# Antenna.net
KiCad netlist of a schematic drawn in Altium Designer
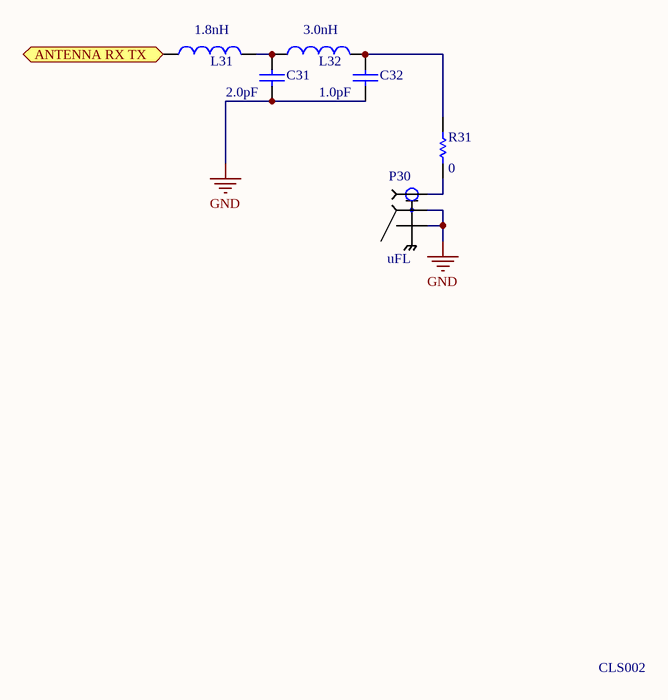
[diagram p0: Antenna.SchDoc]

(export (version "E")
  (design (tool "Eeschema 10.0.6"))
  (components
    (comp (ref "C31")
      (value "2.0pF")
      (footprint "0402_CHIP_FP")
      (fields
        (field (name "MANUFACTURER") "Murata Electronics North America")
        (field (name "MANUFACTURER PART NUMBER") "GJM1555C1H2R0WB01D")
        (field (name "VENDOR PART NUMBER") "490-11205-1-ND")
      )
      (libsource (lib "GenericSymbols") (part "Capacitor_unpolarized_0805"))
    )
    (comp (ref "C32")
      (value "1.0pF")
      (footprint "0402_CHIP_FP")
      (fields
        (field (name "MANUFACTURER") "Murata Electronics North America")
        (field (name "MANUFACTURER PART NUMBER") "GJM1555C1H1R0WB01D")
        (field (name "VENDOR PART NUMBER") "490-11193-1-ND")
      )
      (libsource (lib "GenericSymbols") (part "Capacitor_unpolarized_0805"))
    )
    (comp (ref "L31")
      (value "1.8nH")
      (footprint "0402_CHIP_FP")
      (fields
        (field (name "MANUFACTURER") "Murata Electronics North America")
        (field (name "MANUFACTURER PART NUMBER") "LQP15MN1N8B02D")
        (field (name "VENDOR PART NUMBER") "490-1127-1-ND")
      )
      (libsource (lib "GenericSymbols") (part "Inductor"))
    )
    (comp (ref "L32")
      (value "3.0nH")
      (footprint "0402_CHIP_FP")
      (fields
        (field (name "MANUFACTURER") "Murata Electronics North America")
        (field (name "MANUFACTURER PART NUMBER") "LQP15MN3N0B02D")
        (field (name "VENDOR PART NUMBER") "490-6755-1-ND")
      )
      (libsource (lib "GenericSymbols") (part "Inductor"))
    )
    (comp (ref "P30")
      (value "uFL")
      (footprint "MOLEX_1661")
      (description "uFL SMT Antenna Connector")
      (fields (field (name "MF") "Keystone Electronics") (field (name "MP") "1661"))
      (libsource (lib "1661") (part "1661"))
    )
    (comp (ref "R31")
      (value "0")
      (footprint "0805_CHIP_FP")
      (fields
        (field (name "MANUFACTURER") "Vishay Dale")
        (field (name "MANUFACTURER PART NUMBER") "CRCW08050000Z0EA")
        (field (name "VENDOR PART NUMBER") "541-0.0ACT-ND")
      )
      (libsource (lib "GenericSymbols") (part "Resistor_0805"))
    )
  )
  (nets
    (net (code "1") (name "/ANTENNA RX TX") (class "Default")
      (node (ref "L31") (pin "1") (pinfunction "1_1") (pintype "passive"))
    )
    (net (code "2") (name "GND") (class "Default")
      (node (ref "C31") (pin "1") (pinfunction "1_1") (pintype "passive"))
      (node (ref "C32") (pin "1") (pinfunction "1_1") (pintype "passive"))
      (node (ref "P30") (pin "2") (pinfunction "GND_2") (pintype "passive"))
      (node (ref "P30") (pin "3") (pinfunction "GND_3") (pintype "passive"))
    )
    (net (code "3") (name "Net-(C31-Pad2)") (class "Default")
      (node (ref "C31") (pin "2") (pinfunction "2_2") (pintype "passive"))
      (node (ref "L31") (pin "2") (pinfunction "2_2") (pintype "passive"))
      (node (ref "L32") (pin "1") (pinfunction "1_1") (pintype "passive"))
    )
    (net (code "4") (name "Net-(C32-Pad2)") (class "Default")
      (node (ref "C32") (pin "2") (pinfunction "2_2") (pintype "passive"))
      (node (ref "L32") (pin "2") (pinfunction "2_2") (pintype "passive"))
      (node (ref "R31") (pin "2") (pinfunction "2_2") (pintype "passive"))
    )
    (net (code "5") (name "Net-(P30-SIG)") (class "Default")
      (node (ref "P30") (pin "1") (pinfunction "SIG_1") (pintype "passive"))
      (node (ref "R31") (pin "1") (pinfunction "1_1") (pintype "passive"))
    )
  )
)
